# TamaDecoDumper-LPT-1_1.net
KiCad netlist of a schematic drawn in EAGLE
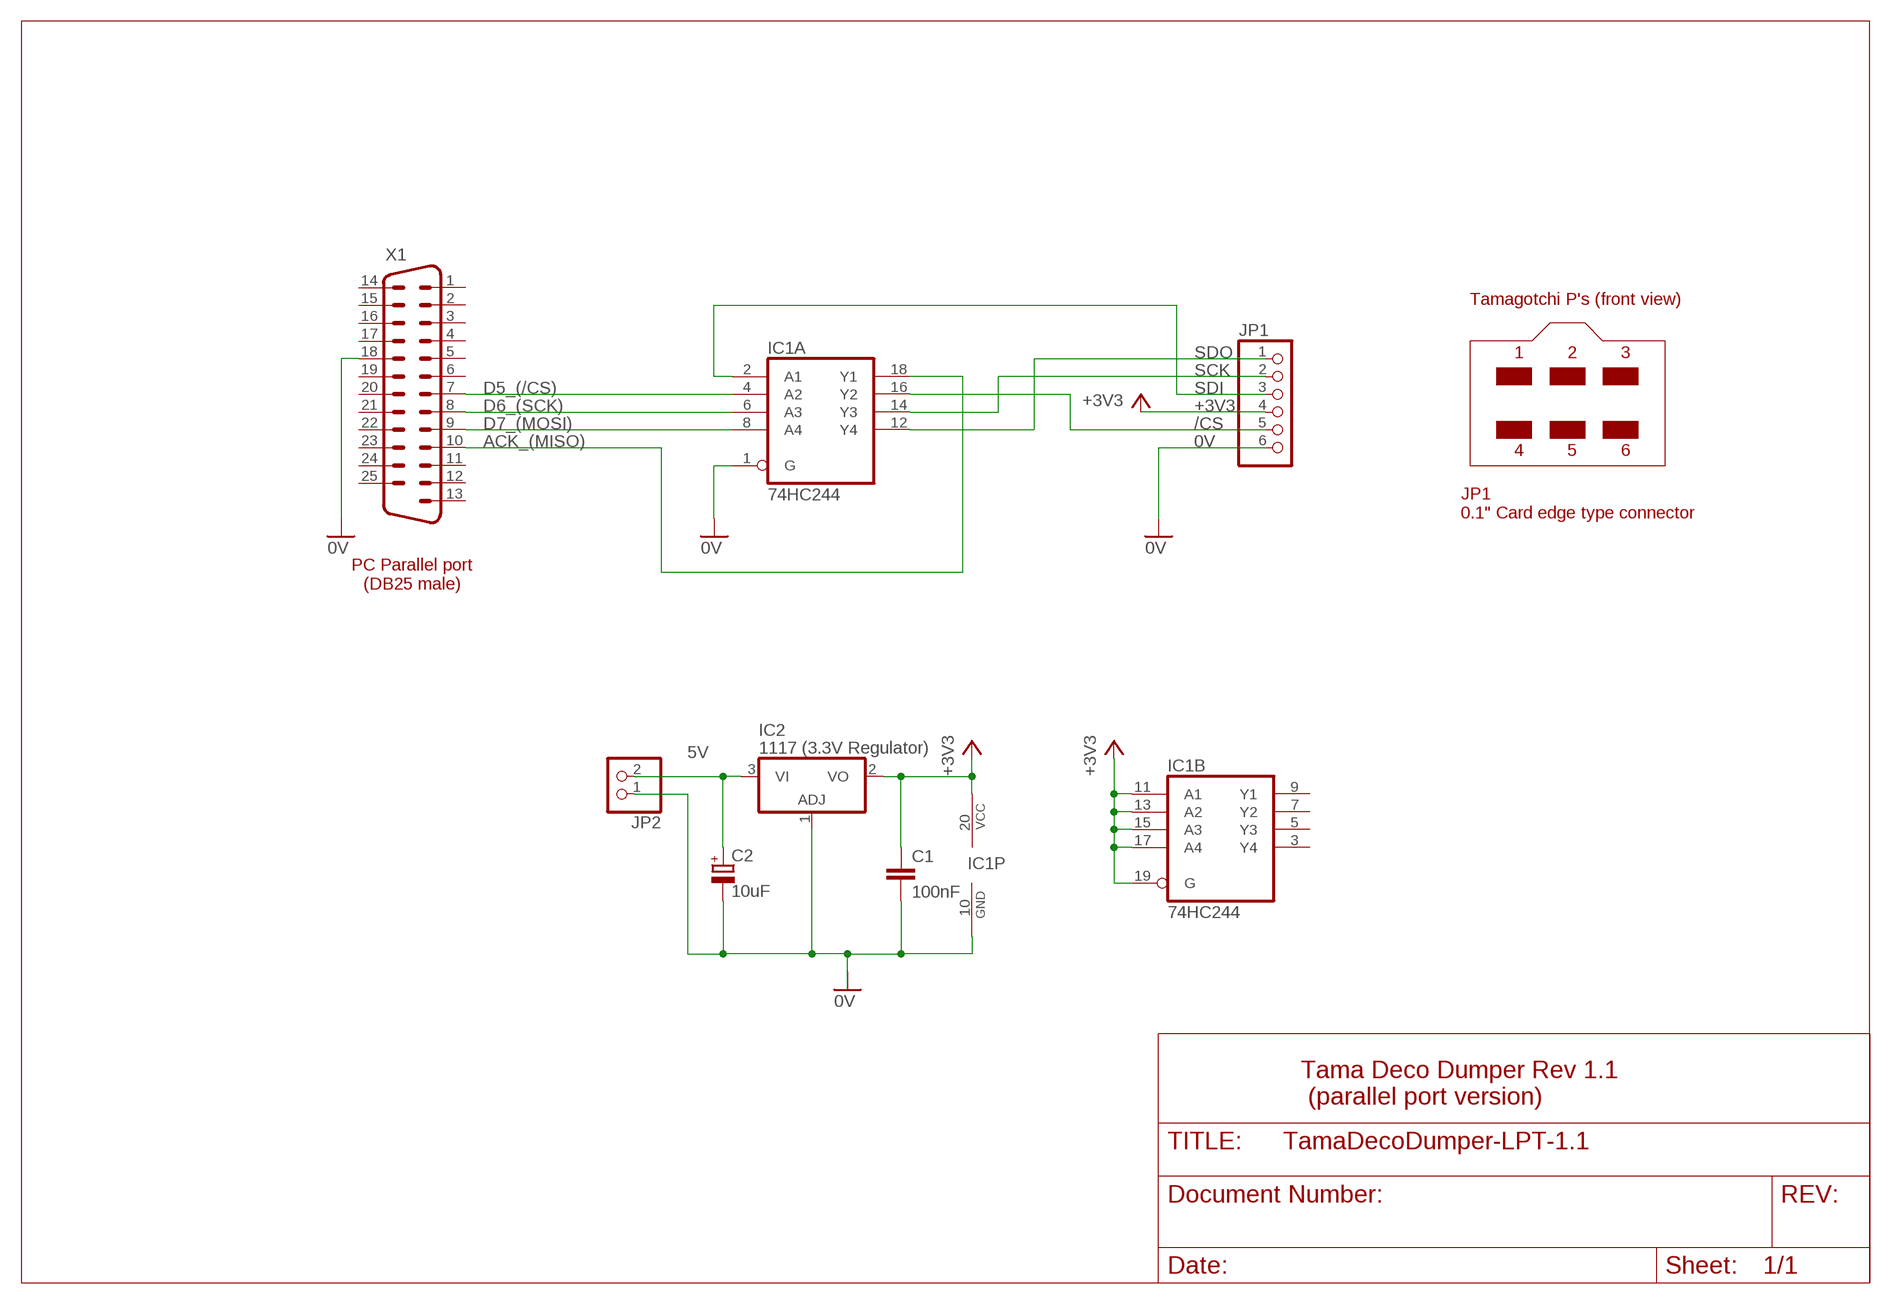
[diagram p0: schematic, sheet 1]

(export (version "E")
  (design (tool "Eeschema 10.0.6"))
  (components
    (comp (ref "C1")
      (value "100nF")
      (footprint "eagle-import:C050-025X075")
      (libsource (lib "eagle-import") (part "C-EU050-025X075"))
    )
    (comp (ref "C2")
      (value "10uF")
      (footprint "eagle-import:E5-6")
      (libsource (lib "eagle-import") (part "CPOL-EUE5-6"))
    )
    (comp (ref "IC1")
      (value "74HC244")
      (footprint "eagle-import:DIL20")
      (libsource (lib "eagle-import") (part "74244NLS"))
    )
    (comp (ref "IC2")
      (value "1117 (3.3V Regulator)")
      (footprint "eagle-import:TO220H")
      (libsource (lib "eagle-import") (part "317T"))
    )
    (comp (ref "JP1")
      (value "PINHD-1X6")
      (footprint "eagle-import:1X06")
      (libsource (lib "eagle-import") (part "PINHD-1X6"))
    )
    (comp (ref "JP2")
      (value "PINHD-1X2")
      (footprint "eagle-import:1X02")
      (libsource (lib "eagle-import") (part "PINHD-1X2"))
    )
    (comp (ref "X1")
      (value "M25HP")
      (footprint "eagle-import:M25HP")
      (libsource (lib "eagle-import") (part "M25HP"))
    )
  )
  (nets
    (net (code "1") (name "+3V3") (class "Default")
      (node (ref "C1") (pin "1") (pinfunction "1_1") (pintype "passive"))
      (node (ref "IC1") (pin "11") (pinfunction "A1_11") (pintype "input"))
      (node (ref "IC1") (pin "13") (pinfunction "A2_13") (pintype "input"))
      (node (ref "IC1") (pin "15") (pinfunction "A3_15") (pintype "input"))
      (node (ref "IC1") (pin "17") (pinfunction "A4_17") (pintype "input"))
      (node (ref "IC1") (pin "19") (pinfunction "G_19") (pintype "input"))
      (node (ref "IC1") (pin "20") (pinfunction "VCC_20") (pintype "power_in"))
      (node (ref "IC2") (pin "2") (pinfunction "VO_2") (pintype "passive"))
      (node (ref "JP1") (pin "4") (pinfunction "4_4") (pintype "passive"))
    )
    (net (code "2") (name "/5V") (class "Default")
      (node (ref "C2") (pin "+") (pinfunction "+_+") (pintype "passive"))
      (node (ref "IC2") (pin "3") (pinfunction "VI_3") (pintype "input"))
      (node (ref "JP2") (pin "2") (pinfunction "2_2") (pintype "passive"))
    )
    (net (code "3") (name "/ACK_(MISO)") (class "Default")
      (node (ref "IC1") (pin "18") (pinfunction "Y1_18") (pintype "tri_state"))
      (node (ref "X1") (pin "10") (pinfunction "10_10") (pintype "passive"))
    )
    (net (code "4") (name "/D5_({slash}CS)") (class "Default")
      (node (ref "IC1") (pin "4") (pinfunction "A2_4") (pintype "input"))
      (node (ref "X1") (pin "7") (pinfunction "7_7") (pintype "passive"))
    )
    (net (code "5") (name "/D6_(SCK)") (class "Default")
      (node (ref "IC1") (pin "6") (pinfunction "A3_6") (pintype "input"))
      (node (ref "X1") (pin "8") (pinfunction "8_8") (pintype "passive"))
    )
    (net (code "6") (name "/D7_(MOSI)") (class "Default")
      (node (ref "IC1") (pin "8") (pinfunction "A4_8") (pintype "input"))
      (node (ref "X1") (pin "9") (pinfunction "9_9") (pintype "passive"))
    )
    (net (code "7") (name "/SCK") (class "Default")
      (node (ref "IC1") (pin "14") (pinfunction "Y3_14") (pintype "tri_state"))
      (node (ref "JP1") (pin "2") (pinfunction "2_2") (pintype "passive"))
    )
    (net (code "8") (name "/SDI") (class "Default")
      (node (ref "IC1") (pin "2") (pinfunction "A1_2") (pintype "input"))
      (node (ref "JP1") (pin "3") (pinfunction "3_3") (pintype "passive"))
    )
    (net (code "9") (name "/SDO") (class "Default")
      (node (ref "IC1") (pin "12") (pinfunction "Y4_12") (pintype "tri_state"))
      (node (ref "JP1") (pin "1") (pinfunction "1_1") (pintype "passive"))
    )
    (net (code "10") (name "/{slash}CS") (class "Default")
      (node (ref "IC1") (pin "16") (pinfunction "Y2_16") (pintype "tri_state"))
      (node (ref "JP1") (pin "5") (pinfunction "5_5") (pintype "passive"))
    )
    (net (code "11") (name "0V") (class "Default")
      (node (ref "C1") (pin "2") (pinfunction "2_2") (pintype "passive"))
      (node (ref "C2") (pin "-") (pinfunction "-_-") (pintype "passive"))
      (node (ref "IC1") (pin "1") (pinfunction "G_1") (pintype "input"))
      (node (ref "IC1") (pin "10") (pinfunction "GND_10") (pintype "power_in"))
      (node (ref "IC2") (pin "1") (pinfunction "ADJ_1") (pintype "input"))
      (node (ref "JP1") (pin "6") (pinfunction "6_6") (pintype "passive"))
      (node (ref "JP2") (pin "1") (pinfunction "1_1") (pintype "passive"))
      (node (ref "X1") (pin "18") (pinfunction "18_18") (pintype "passive"))
    )
    (net (code "12") (name "unconnected-(IC1B-Y1-Pad9)") (class "Default")
      (node (ref "IC1") (pin "9") (pinfunction "Y1_9") (pintype "tri_state"))
    )
    (net (code "13") (name "unconnected-(IC1B-Y2-Pad7)") (class "Default")
      (node (ref "IC1") (pin "7") (pinfunction "Y2_7") (pintype "tri_state"))
    )
    (net (code "14") (name "unconnected-(IC1B-Y3-Pad5)") (class "Default")
      (node (ref "IC1") (pin "5") (pinfunction "Y3_5") (pintype "tri_state"))
    )
    (net (code "15") (name "unconnected-(IC1B-Y4-Pad3)") (class "Default")
      (node (ref "IC1") (pin "3") (pinfunction "Y4_3") (pintype "tri_state"))
    )
    (net (code "16") (name "unconnected-(X1-Pad1)") (class "Default")
      (node (ref "X1") (pin "1") (pinfunction "1_1") (pintype "passive"))
    )
    (net (code "17") (name "unconnected-(X1-Pad2)") (class "Default")
      (node (ref "X1") (pin "2") (pinfunction "2_2") (pintype "passive"))
    )
    (net (code "18") (name "unconnected-(X1-Pad3)") (class "Default")
      (node (ref "X1") (pin "3") (pinfunction "3_3") (pintype "passive"))
    )
    (net (code "19") (name "unconnected-(X1-Pad4)") (class "Default")
      (node (ref "X1") (pin "4") (pinfunction "4_4") (pintype "passive"))
    )
    (net (code "20") (name "unconnected-(X1-Pad5)") (class "Default")
      (node (ref "X1") (pin "5") (pinfunction "5_5") (pintype "passive"))
    )
    (net (code "21") (name "unconnected-(X1-Pad6)") (class "Default")
      (node (ref "X1") (pin "6") (pinfunction "6_6") (pintype "passive"))
    )
    (net (code "22") (name "unconnected-(X1-Pad11)") (class "Default")
      (node (ref "X1") (pin "11") (pinfunction "11_11") (pintype "passive"))
    )
    (net (code "23") (name "unconnected-(X1-Pad12)") (class "Default")
      (node (ref "X1") (pin "12") (pinfunction "12_12") (pintype "passive"))
    )
    (net (code "24") (name "unconnected-(X1-Pad13)") (class "Default")
      (node (ref "X1") (pin "13") (pinfunction "13_13") (pintype "passive"))
    )
    (net (code "25") (name "unconnected-(X1-Pad14)") (class "Default")
      (node (ref "X1") (pin "14") (pinfunction "14_14") (pintype "passive"))
    )
    (net (code "26") (name "unconnected-(X1-Pad15)") (class "Default")
      (node (ref "X1") (pin "15") (pinfunction "15_15") (pintype "passive"))
    )
    (net (code "27") (name "unconnected-(X1-Pad16)") (class "Default")
      (node (ref "X1") (pin "16") (pinfunction "16_16") (pintype "passive"))
    )
    (net (code "28") (name "unconnected-(X1-Pad17)") (class "Default")
      (node (ref "X1") (pin "17") (pinfunction "17_17") (pintype "passive"))
    )
    (net (code "29") (name "unconnected-(X1-Pad19)") (class "Default")
      (node (ref "X1") (pin "19") (pinfunction "19_19") (pintype "passive"))
    )
    (net (code "30") (name "unconnected-(X1-Pad20)") (class "Default")
      (node (ref "X1") (pin "20") (pinfunction "20_20") (pintype "passive"))
    )
    (net (code "31") (name "unconnected-(X1-Pad21)") (class "Default")
      (node (ref "X1") (pin "21") (pinfunction "21_21") (pintype "passive"))
    )
    (net (code "32") (name "unconnected-(X1-Pad22)") (class "Default")
      (node (ref "X1") (pin "22") (pinfunction "22_22") (pintype "passive"))
    )
    (net (code "33") (name "unconnected-(X1-Pad23)") (class "Default")
      (node (ref "X1") (pin "23") (pinfunction "23_23") (pintype "passive"))
    )
    (net (code "34") (name "unconnected-(X1-Pad24)") (class "Default")
      (node (ref "X1") (pin "24") (pinfunction "24_24") (pintype "passive"))
    )
    (net (code "35") (name "unconnected-(X1-Pad25)") (class "Default")
      (node (ref "X1") (pin "25") (pinfunction "25_25") (pintype "passive"))
    )
  )
)
